# Hviezdy.net
KiCad netlist of a schematic drawn in EAGLE
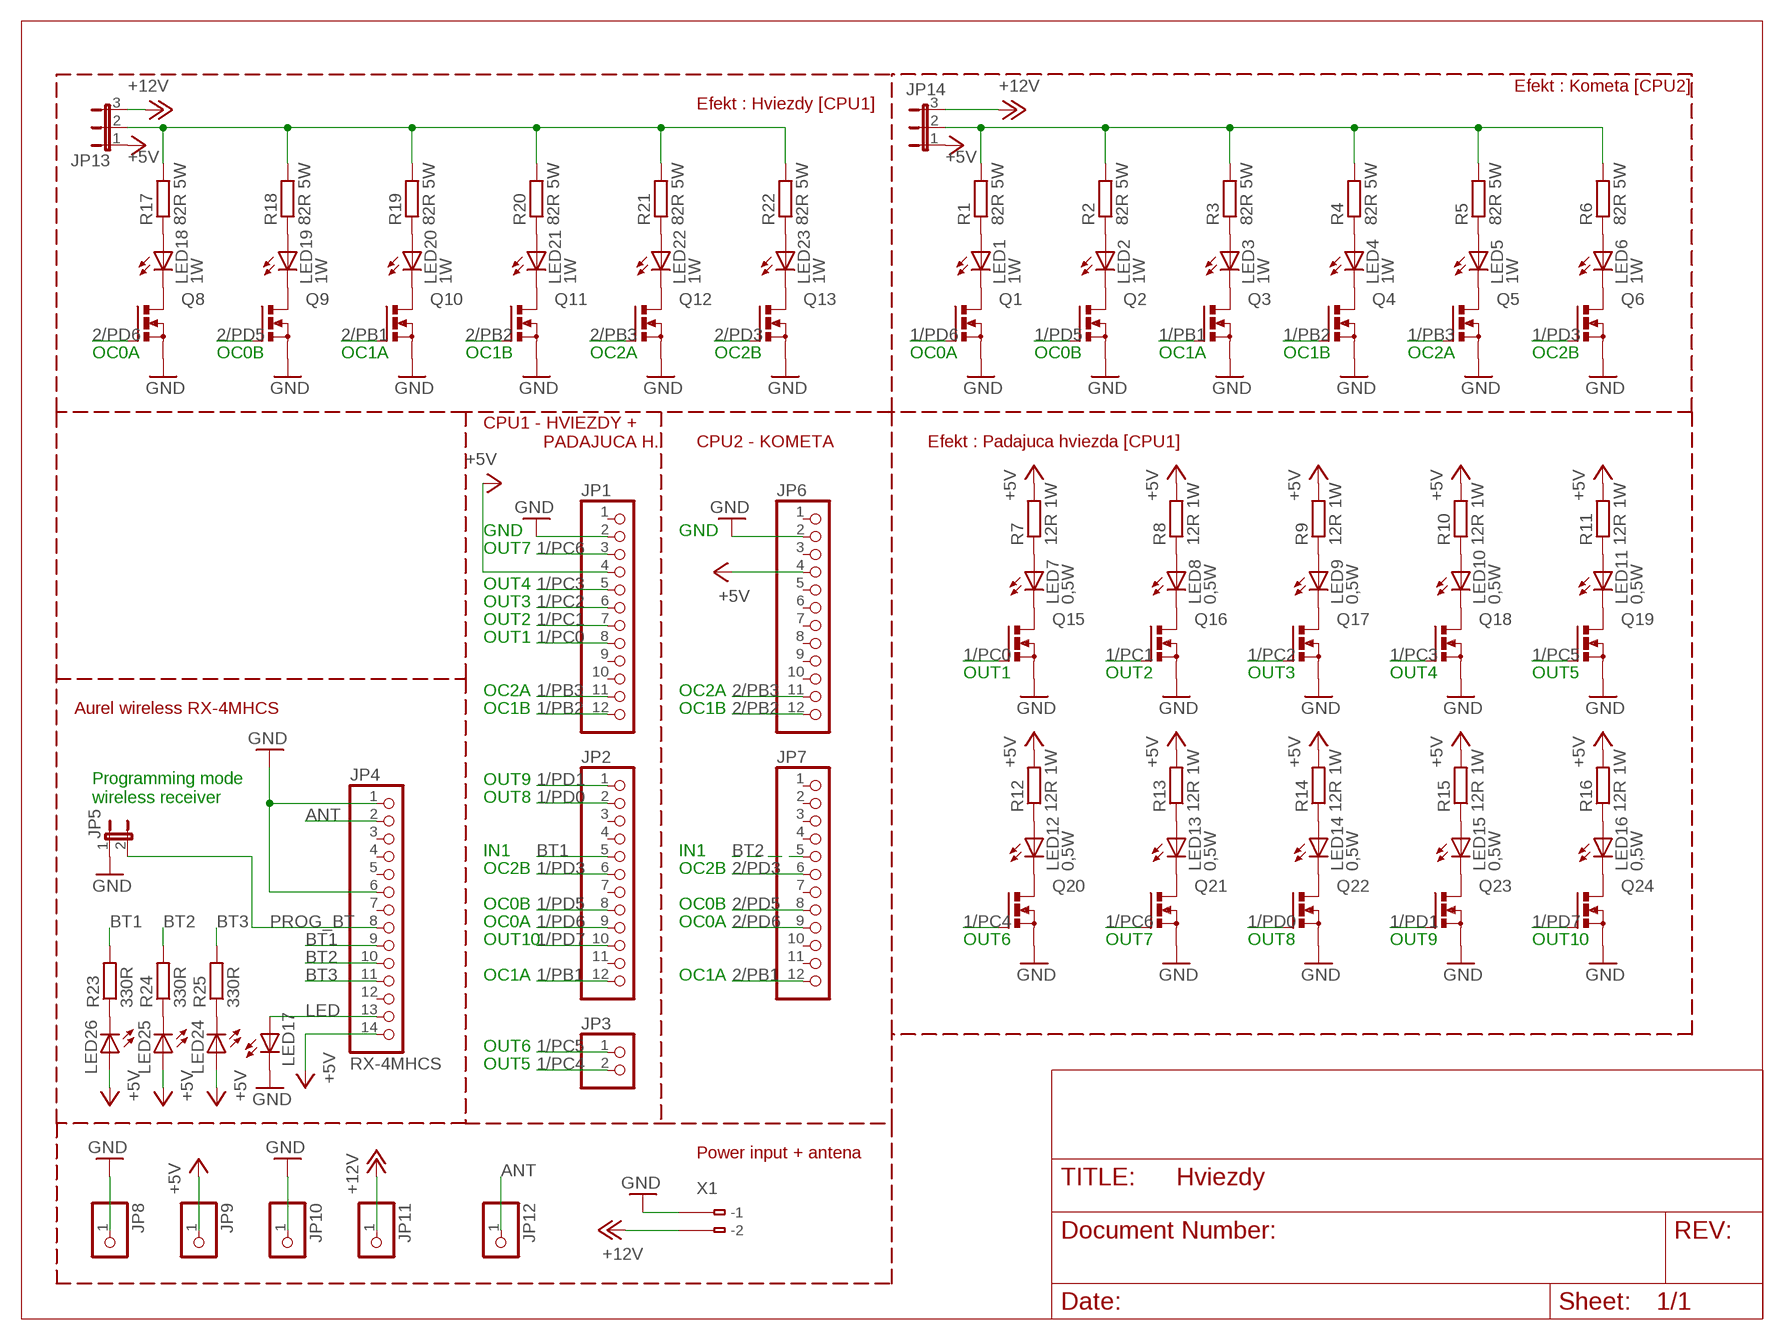
[diagram p0: schematic, sheet 1]

(export (version "E")
  (design (tool "Eeschema 10.0.6"))
  (components
    (comp (ref "JP1")
      (value "PINHD-1X12")
      (footprint "eagle-import:1X12")
      (libsource (lib "eagle-import") (part "PINHD-1X12"))
    )
    (comp (ref "JP2")
      (value "PINHD-1X12")
      (footprint "eagle-import:1X12")
      (libsource (lib "eagle-import") (part "PINHD-1X12"))
    )
    (comp (ref "JP3")
      (value "PINHD-1X2")
      (footprint "eagle-import:1X02")
      (libsource (lib "eagle-import") (part "PINHD-1X2"))
    )
    (comp (ref "JP4")
      (value "RX-4MHCS")
      (footprint "eagle-import:1X14")
      (libsource (lib "eagle-import") (part "PINHD-1X14"))
    )
    (comp (ref "JP5")
      (value "JP1E")
      (footprint "eagle-import:JP1")
      (libsource (lib "eagle-import") (part "JP1E"))
    )
    (comp (ref "JP6")
      (value "PINHD-1X12")
      (footprint "eagle-import:1X12")
      (libsource (lib "eagle-import") (part "PINHD-1X12"))
    )
    (comp (ref "JP7")
      (value "PINHD-1X12")
      (footprint "eagle-import:1X12")
      (libsource (lib "eagle-import") (part "PINHD-1X12"))
    )
    (comp (ref "JP8")
      (value "PINHD-1X1")
      (footprint "eagle-import:1X01")
      (libsource (lib "eagle-import") (part "PINHD-1X1"))
    )
    (comp (ref "JP9")
      (value "PINHD-1X1")
      (footprint "eagle-import:1X01")
      (libsource (lib "eagle-import") (part "PINHD-1X1"))
    )
    (comp (ref "JP10")
      (value "PINHD-1X1")
      (footprint "eagle-import:1X01")
      (libsource (lib "eagle-import") (part "PINHD-1X1"))
    )
    (comp (ref "JP11")
      (value "PINHD-1X1")
      (footprint "eagle-import:1X01")
      (libsource (lib "eagle-import") (part "PINHD-1X1"))
    )
    (comp (ref "JP12")
      (value "PINHD-1X1")
      (footprint "eagle-import:1X01")
      (libsource (lib "eagle-import") (part "PINHD-1X1"))
    )
    (comp (ref "JP13")
      (value "JP2E")
      (footprint "eagle-import:JP2")
      (libsource (lib "eagle-import") (part "JP2E"))
    )
    (comp (ref "JP14")
      (value "JP2E")
      (footprint "eagle-import:JP2")
      (libsource (lib "eagle-import") (part "JP2E"))
    )
    (comp (ref "LED1")
      (value "1W")
      (footprint "eagle-import:LED5MM")
      (libsource (lib "eagle-import") (part "LED5MM"))
    )
    (comp (ref "LED2")
      (value "1W")
      (footprint "eagle-import:LED5MM")
      (libsource (lib "eagle-import") (part "LED5MM"))
    )
    (comp (ref "LED3")
      (value "1W")
      (footprint "eagle-import:LED5MM")
      (libsource (lib "eagle-import") (part "LED5MM"))
    )
    (comp (ref "LED4")
      (value "1W")
      (footprint "eagle-import:LED5MM")
      (libsource (lib "eagle-import") (part "LED5MM"))
    )
    (comp (ref "LED5")
      (value "1W")
      (footprint "eagle-import:LED5MM")
      (libsource (lib "eagle-import") (part "LED5MM"))
    )
    (comp (ref "LED6")
      (value "1W")
      (footprint "eagle-import:LED5MM")
      (libsource (lib "eagle-import") (part "LED5MM"))
    )
    (comp (ref "LED7")
      (value "0,5W")
      (footprint "eagle-import:LED10MM")
      (libsource (lib "eagle-import") (part "LED10MM"))
    )
    (comp (ref "LED8")
      (value "0,5W")
      (footprint "eagle-import:LED10MM")
      (libsource (lib "eagle-import") (part "LED10MM"))
    )
    (comp (ref "LED9")
      (value "0,5W")
      (footprint "eagle-import:LED10MM")
      (libsource (lib "eagle-import") (part "LED10MM"))
    )
    (comp (ref "LED10")
      (value "0,5W")
      (footprint "eagle-import:LED10MM")
      (libsource (lib "eagle-import") (part "LED10MM"))
    )
    (comp (ref "LED11")
      (value "0,5W")
      (footprint "eagle-import:LED10MM")
      (libsource (lib "eagle-import") (part "LED10MM"))
    )
    (comp (ref "LED12")
      (value "0,5W")
      (footprint "eagle-import:LED10MM")
      (libsource (lib "eagle-import") (part "LED10MM"))
    )
    (comp (ref "LED13")
      (value "0,5W")
      (footprint "eagle-import:LED10MM")
      (libsource (lib "eagle-import") (part "LED10MM"))
    )
    (comp (ref "LED14")
      (value "0,5W")
      (footprint "eagle-import:LED10MM")
      (libsource (lib "eagle-import") (part "LED10MM"))
    )
    (comp (ref "LED15")
      (value "0,5W")
      (footprint "eagle-import:LED10MM")
      (libsource (lib "eagle-import") (part "LED10MM"))
    )
    (comp (ref "LED16")
      (value "0,5W")
      (footprint "eagle-import:LED10MM")
      (libsource (lib "eagle-import") (part "LED10MM"))
    )
    (comp (ref "LED17")
      (value "LED3MM")
      (footprint "eagle-import:LED3MM")
      (libsource (lib "eagle-import") (part "LED3MM"))
    )
    (comp (ref "LED18")
      (value "1W")
      (footprint "eagle-import:LED5MM")
      (libsource (lib "eagle-import") (part "LED5MM"))
    )
    (comp (ref "LED19")
      (value "1W")
      (footprint "eagle-import:LED5MM")
      (libsource (lib "eagle-import") (part "LED5MM"))
    )
    (comp (ref "LED20")
      (value "1W")
      (footprint "eagle-import:LED5MM")
      (libsource (lib "eagle-import") (part "LED5MM"))
    )
    (comp (ref "LED21")
      (value "1W")
      (footprint "eagle-import:LED5MM")
      (libsource (lib "eagle-import") (part "LED5MM"))
    )
    (comp (ref "LED22")
      (value "1W")
      (footprint "eagle-import:LED5MM")
      (libsource (lib "eagle-import") (part "LED5MM"))
    )
    (comp (ref "LED23")
      (value "1W")
      (footprint "eagle-import:LED5MM")
      (libsource (lib "eagle-import") (part "LED5MM"))
    )
    (comp (ref "LED24")
      (value "LED3MM")
      (footprint "eagle-import:LED3MM")
      (libsource (lib "eagle-import") (part "LED3MM"))
    )
    (comp (ref "LED25")
      (value "LED3MM")
      (footprint "eagle-import:LED3MM")
      (libsource (lib "eagle-import") (part "LED3MM"))
    )
    (comp (ref "LED26")
      (value "LED3MM")
      (footprint "eagle-import:LED3MM")
      (libsource (lib "eagle-import") (part "LED3MM"))
    )
    (comp (ref "Q1")
      (value "PMOSFET_NTO220BV")
      (footprint "eagle-import:TO220BV")
      (libsource (lib "eagle-import") (part "PMOSFET_NTO220BV"))
    )
    (comp (ref "Q2")
      (value "PMOSFET_NTO220BV")
      (footprint "eagle-import:TO220BV")
      (libsource (lib "eagle-import") (part "PMOSFET_NTO220BV"))
    )
    (comp (ref "Q3")
      (value "PMOSFET_NTO220BV")
      (footprint "eagle-import:TO220BV")
      (libsource (lib "eagle-import") (part "PMOSFET_NTO220BV"))
    )
    (comp (ref "Q4")
      (value "PMOSFET_NTO220BV")
      (footprint "eagle-import:TO220BV")
      (libsource (lib "eagle-import") (part "PMOSFET_NTO220BV"))
    )
    (comp (ref "Q5")
      (value "PMOSFET_NTO220BV")
      (footprint "eagle-import:TO220BV")
      (libsource (lib "eagle-import") (part "PMOSFET_NTO220BV"))
    )
    (comp (ref "Q6")
      (value "PMOSFET_NTO220BV")
      (footprint "eagle-import:TO220BV")
      (libsource (lib "eagle-import") (part "PMOSFET_NTO220BV"))
    )
    (comp (ref "Q8")
      (value "PMOSFET_NTO220BV")
      (footprint "eagle-import:TO220BV")
      (libsource (lib "eagle-import") (part "PMOSFET_NTO220BV"))
    )
    (comp (ref "Q9")
      (value "PMOSFET_NTO220BV")
      (footprint "eagle-import:TO220BV")
      (libsource (lib "eagle-import") (part "PMOSFET_NTO220BV"))
    )
    (comp (ref "Q10")
      (value "PMOSFET_NTO220BV")
      (footprint "eagle-import:TO220BV")
      (libsource (lib "eagle-import") (part "PMOSFET_NTO220BV"))
    )
    (comp (ref "Q11")
      (value "PMOSFET_NTO220BV")
      (footprint "eagle-import:TO220BV")
      (libsource (lib "eagle-import") (part "PMOSFET_NTO220BV"))
    )
    (comp (ref "Q12")
      (value "PMOSFET_NTO220BV")
      (footprint "eagle-import:TO220BV")
      (libsource (lib "eagle-import") (part "PMOSFET_NTO220BV"))
    )
    (comp (ref "Q13")
      (value "PMOSFET_NTO220BV")
      (footprint "eagle-import:TO220BV")
      (libsource (lib "eagle-import") (part "PMOSFET_NTO220BV"))
    )
    (comp (ref "Q15")
      (value "PMOSFET_NTO220BV")
      (footprint "eagle-import:TO220BV")
      (libsource (lib "eagle-import") (part "PMOSFET_NTO220BV"))
    )
    (comp (ref "Q16")
      (value "PMOSFET_NTO220BV")
      (footprint "eagle-import:TO220BV")
      (libsource (lib "eagle-import") (part "PMOSFET_NTO220BV"))
    )
    (comp (ref "Q17")
      (value "PMOSFET_NTO220BV")
      (footprint "eagle-import:TO220BV")
      (libsource (lib "eagle-import") (part "PMOSFET_NTO220BV"))
    )
    (comp (ref "Q18")
      (value "PMOSFET_NTO220BV")
      (footprint "eagle-import:TO220BV")
      (libsource (lib "eagle-import") (part "PMOSFET_NTO220BV"))
    )
    (comp (ref "Q19")
      (value "PMOSFET_NTO220BV")
      (footprint "eagle-import:TO220BV")
      (libsource (lib "eagle-import") (part "PMOSFET_NTO220BV"))
    )
    (comp (ref "Q20")
      (value "PMOSFET_NTO220BV")
      (footprint "eagle-import:TO220BV")
      (libsource (lib "eagle-import") (part "PMOSFET_NTO220BV"))
    )
    (comp (ref "Q21")
      (value "PMOSFET_NTO220BV")
      (footprint "eagle-import:TO220BV")
      (libsource (lib "eagle-import") (part "PMOSFET_NTO220BV"))
    )
    (comp (ref "Q22")
      (value "PMOSFET_NTO220BV")
      (footprint "eagle-import:TO220BV")
      (libsource (lib "eagle-import") (part "PMOSFET_NTO220BV"))
    )
    (comp (ref "Q23")
      (value "PMOSFET_NTO220BV")
      (footprint "eagle-import:TO220BV")
      (libsource (lib "eagle-import") (part "PMOSFET_NTO220BV"))
    )
    (comp (ref "Q24")
      (value "PMOSFET_NTO220BV")
      (footprint "eagle-import:TO220BV")
      (libsource (lib "eagle-import") (part "PMOSFET_NTO220BV"))
    )
    (comp (ref "R1")
      (value "82R 5W")
      (footprint "eagle-import:0922V")
      (libsource (lib "eagle-import") (part "R-EU_0922V"))
    )
    (comp (ref "R2")
      (value "82R 5W")
      (footprint "eagle-import:0922V")
      (libsource (lib "eagle-import") (part "R-EU_0922V"))
    )
    (comp (ref "R3")
      (value "82R 5W")
      (footprint "eagle-import:0922V")
      (libsource (lib "eagle-import") (part "R-EU_0922V"))
    )
    (comp (ref "R4")
      (value "82R 5W")
      (footprint "eagle-import:0922V")
      (libsource (lib "eagle-import") (part "R-EU_0922V"))
    )
    (comp (ref "R5")
      (value "82R 5W")
      (footprint "eagle-import:0922V")
      (libsource (lib "eagle-import") (part "R-EU_0922V"))
    )
    (comp (ref "R6")
      (value "82R 5W")
      (footprint "eagle-import:0922V")
      (libsource (lib "eagle-import") (part "R-EU_0922V"))
    )
    (comp (ref "R7")
      (value "12R 1W")
      (footprint "eagle-import:0309_12")
      (libsource (lib "eagle-import") (part "R-EU_0309/12"))
    )
    (comp (ref "R8")
      (value "12R 1W")
      (footprint "eagle-import:0309_12")
      (libsource (lib "eagle-import") (part "R-EU_0309/12"))
    )
    (comp (ref "R9")
      (value "12R 1W")
      (footprint "eagle-import:0309_12")
      (libsource (lib "eagle-import") (part "R-EU_0309/12"))
    )
    (comp (ref "R10")
      (value "12R 1W")
      (footprint "eagle-import:0309_12")
      (libsource (lib "eagle-import") (part "R-EU_0309/12"))
    )
    (comp (ref "R11")
      (value "12R 1W")
      (footprint "eagle-import:0309_12")
      (libsource (lib "eagle-import") (part "R-EU_0309/12"))
    )
    (comp (ref "R12")
      (value "12R 1W")
      (footprint "eagle-import:0309_12")
      (libsource (lib "eagle-import") (part "R-EU_0309/12"))
    )
    (comp (ref "R13")
      (value "12R 1W")
      (footprint "eagle-import:0309_12")
      (libsource (lib "eagle-import") (part "R-EU_0309/12"))
    )
    (comp (ref "R14")
      (value "12R 1W")
      (footprint "eagle-import:0309_12")
      (libsource (lib "eagle-import") (part "R-EU_0309/12"))
    )
    (comp (ref "R15")
      (value "12R 1W")
      (footprint "eagle-import:0309_12")
      (libsource (lib "eagle-import") (part "R-EU_0309/12"))
    )
    (comp (ref "R16")
      (value "12R 1W")
      (footprint "eagle-import:0309_12")
      (libsource (lib "eagle-import") (part "R-EU_0309/12"))
    )
    (comp (ref "R17")
      (value "82R 5W")
      (footprint "eagle-import:0922V")
      (libsource (lib "eagle-import") (part "R-EU_0922V"))
    )
    (comp (ref "R18")
      (value "82R 5W")
      (footprint "eagle-import:0922V")
      (libsource (lib "eagle-import") (part "R-EU_0922V"))
    )
    (comp (ref "R19")
      (value "82R 5W")
      (footprint "eagle-import:0922V")
      (libsource (lib "eagle-import") (part "R-EU_0922V"))
    )
    (comp (ref "R20")
      (value "82R 5W")
      (footprint "eagle-import:0922V")
      (libsource (lib "eagle-import") (part "R-EU_0922V"))
    )
    (comp (ref "R21")
      (value "82R 5W")
      (footprint "eagle-import:0922V")
      (libsource (lib "eagle-import") (part "R-EU_0922V"))
    )
    (comp (ref "R22")
      (value "82R 5W")
      (footprint "eagle-import:0922V")
      (libsource (lib "eagle-import") (part "R-EU_0922V"))
    )
    (comp (ref "R23")
      (value "330R")
      (footprint "eagle-import:0207_12")
      (libsource (lib "eagle-import") (part "resistor_R-EU_0207/12"))
    )
    (comp (ref "R24")
      (value "330R")
      (footprint "eagle-import:0207_12")
      (libsource (lib "eagle-import") (part "resistor_R-EU_0207/12"))
    )
    (comp (ref "R25")
      (value "330R")
      (footprint "eagle-import:0207_12")
      (libsource (lib "eagle-import") (part "resistor_R-EU_0207/12"))
    )
    (comp (ref "X1")
      (value "234-202")
      (footprint "eagle-import:234-202")
      (libsource (lib "eagle-import") (part "234-202"))
    )
  )
  (nets
    (net (code "1") (name "+5V") (class "Default")
      (node (ref "JP1") (pin "4") (pinfunction "4_4") (pintype "passive"))
      (node (ref "JP13") (pin "1") (pinfunction "1_1") (pintype "passive"))
      (node (ref "JP14") (pin "1") (pinfunction "1_1") (pintype "passive"))
      (node (ref "JP4") (pin "14") (pinfunction "14_14") (pintype "passive"))
      (node (ref "JP6") (pin "4") (pinfunction "4_4") (pintype "passive"))
      (node (ref "JP9") (pin "1") (pinfunction "1_1") (pintype "passive"))
      (node (ref "LED24") (pin "A") (pinfunction "A_A") (pintype "passive"))
      (node (ref "LED25") (pin "A") (pinfunction "A_A") (pintype "passive"))
      (node (ref "LED26") (pin "A") (pinfunction "A_A") (pintype "passive"))
      (node (ref "R10") (pin "2") (pinfunction "2_2") (pintype "passive"))
      (node (ref "R11") (pin "2") (pinfunction "2_2") (pintype "passive"))
      (node (ref "R12") (pin "2") (pinfunction "2_2") (pintype "passive"))
      (node (ref "R13") (pin "2") (pinfunction "2_2") (pintype "passive"))
      (node (ref "R14") (pin "2") (pinfunction "2_2") (pintype "passive"))
      (node (ref "R15") (pin "2") (pinfunction "2_2") (pintype "passive"))
      (node (ref "R16") (pin "2") (pinfunction "2_2") (pintype "passive"))
      (node (ref "R7") (pin "2") (pinfunction "2_2") (pintype "passive"))
      (node (ref "R8") (pin "2") (pinfunction "2_2") (pintype "passive"))
      (node (ref "R9") (pin "2") (pinfunction "2_2") (pintype "passive"))
    )
    (net (code "2") (name "+12V") (class "Default")
      (node (ref "JP11") (pin "1") (pinfunction "1_1") (pintype "passive"))
      (node (ref "JP13") (pin "3") (pinfunction "3_3") (pintype "passive"))
      (node (ref "JP14") (pin "3") (pinfunction "3_3") (pintype "passive"))
      (node (ref "X1") (pin "B2") (pinfunction "B-2_B2") (pintype "passive"))
    )
    (net (code "3") (name "/1{slash}PB1") (class "Default")
      (node (ref "JP2") (pin "12") (pinfunction "12_12") (pintype "passive"))
      (node (ref "Q3") (pin "G") (pinfunction "G_G") (pintype "passive"))
    )
    (net (code "4") (name "/1{slash}PB2") (class "Default")
      (node (ref "JP1") (pin "12") (pinfunction "12_12") (pintype "passive"))
      (node (ref "Q4") (pin "G") (pinfunction "G_G") (pintype "passive"))
    )
    (net (code "5") (name "/1{slash}PB3") (class "Default")
      (node (ref "JP1") (pin "11") (pinfunction "11_11") (pintype "passive"))
      (node (ref "Q5") (pin "G") (pinfunction "G_G") (pintype "passive"))
    )
    (net (code "6") (name "/1{slash}PC0") (class "Default")
      (node (ref "JP1") (pin "8") (pinfunction "8_8") (pintype "passive"))
      (node (ref "Q15") (pin "G") (pinfunction "G_G") (pintype "passive"))
    )
    (net (code "7") (name "/1{slash}PC1") (class "Default")
      (node (ref "JP1") (pin "7") (pinfunction "7_7") (pintype "passive"))
      (node (ref "Q16") (pin "G") (pinfunction "G_G") (pintype "passive"))
    )
    (net (code "8") (name "/1{slash}PC2") (class "Default")
      (node (ref "JP1") (pin "6") (pinfunction "6_6") (pintype "passive"))
      (node (ref "Q17") (pin "G") (pinfunction "G_G") (pintype "passive"))
    )
    (net (code "9") (name "/1{slash}PC3") (class "Default")
      (node (ref "JP1") (pin "5") (pinfunction "5_5") (pintype "passive"))
      (node (ref "Q18") (pin "G") (pinfunction "G_G") (pintype "passive"))
    )
    (net (code "10") (name "/1{slash}PC4") (class "Default")
      (node (ref "JP3") (pin "2") (pinfunction "2_2") (pintype "passive"))
      (node (ref "Q20") (pin "G") (pinfunction "G_G") (pintype "passive"))
    )
    (net (code "11") (name "/1{slash}PC5") (class "Default")
      (node (ref "JP3") (pin "1") (pinfunction "1_1") (pintype "passive"))
      (node (ref "Q19") (pin "G") (pinfunction "G_G") (pintype "passive"))
    )
    (net (code "12") (name "/1{slash}PC6") (class "Default")
      (node (ref "JP1") (pin "3") (pinfunction "3_3") (pintype "passive"))
      (node (ref "Q21") (pin "G") (pinfunction "G_G") (pintype "passive"))
    )
    (net (code "13") (name "/1{slash}PD0") (class "Default")
      (node (ref "JP2") (pin "2") (pinfunction "2_2") (pintype "passive"))
      (node (ref "Q22") (pin "G") (pinfunction "G_G") (pintype "passive"))
    )
    (net (code "14") (name "/1{slash}PD1") (class "Default")
      (node (ref "JP2") (pin "1") (pinfunction "1_1") (pintype "passive"))
      (node (ref "Q23") (pin "G") (pinfunction "G_G") (pintype "passive"))
    )
    (net (code "15") (name "/1{slash}PD3") (class "Default")
      (node (ref "JP2") (pin "6") (pinfunction "6_6") (pintype "passive"))
      (node (ref "Q6") (pin "G") (pinfunction "G_G") (pintype "passive"))
    )
    (net (code "16") (name "/1{slash}PD5") (class "Default")
      (node (ref "JP2") (pin "8") (pinfunction "8_8") (pintype "passive"))
      (node (ref "Q2") (pin "G") (pinfunction "G_G") (pintype "passive"))
    )
    (net (code "17") (name "/1{slash}PD6") (class "Default")
      (node (ref "JP2") (pin "9") (pinfunction "9_9") (pintype "passive"))
      (node (ref "Q1") (pin "G") (pinfunction "G_G") (pintype "passive"))
    )
    (net (code "18") (name "/1{slash}PD7") (class "Default")
      (node (ref "JP2") (pin "10") (pinfunction "10_10") (pintype "passive"))
      (node (ref "Q24") (pin "G") (pinfunction "G_G") (pintype "passive"))
    )
    (net (code "19") (name "/2{slash}PB1") (class "Default")
      (node (ref "JP7") (pin "12") (pinfunction "12_12") (pintype "passive"))
      (node (ref "Q10") (pin "G") (pinfunction "G_G") (pintype "passive"))
    )
    (net (code "20") (name "/2{slash}PB2") (class "Default")
      (node (ref "JP6") (pin "12") (pinfunction "12_12") (pintype "passive"))
      (node (ref "Q11") (pin "G") (pinfunction "G_G") (pintype "passive"))
    )
    (net (code "21") (name "/2{slash}PB3") (class "Default")
      (node (ref "JP6") (pin "11") (pinfunction "11_11") (pintype "passive"))
      (node (ref "Q12") (pin "G") (pinfunction "G_G") (pintype "passive"))
    )
    (net (code "22") (name "/2{slash}PD3") (class "Default")
      (node (ref "JP7") (pin "6") (pinfunction "6_6") (pintype "passive"))
      (node (ref "Q13") (pin "G") (pinfunction "G_G") (pintype "passive"))
    )
    (net (code "23") (name "/2{slash}PD5") (class "Default")
      (node (ref "JP7") (pin "8") (pinfunction "8_8") (pintype "passive"))
      (node (ref "Q9") (pin "G") (pinfunction "G_G") (pintype "passive"))
    )
    (net (code "24") (name "/2{slash}PD6") (class "Default")
      (node (ref "JP7") (pin "9") (pinfunction "9_9") (pintype "passive"))
      (node (ref "Q8") (pin "G") (pinfunction "G_G") (pintype "passive"))
    )
    (net (code "25") (name "/ANT") (class "Default")
      (node (ref "JP12") (pin "1") (pinfunction "1_1") (pintype "passive"))
      (node (ref "JP4") (pin "2") (pinfunction "2_2") (pintype "passive"))
    )
    (net (code "26") (name "/BT1") (class "Default")
      (node (ref "JP2") (pin "5") (pinfunction "5_5") (pintype "passive"))
      (node (ref "JP4") (pin "9") (pinfunction "9_9") (pintype "passive"))
      (node (ref "R23") (pin "2") (pinfunction "2_2") (pintype "passive"))
    )
    (net (code "27") (name "/BT2") (class "Default")
      (node (ref "JP4") (pin "10") (pinfunction "10_10") (pintype "passive"))
      (node (ref "JP7") (pin "5") (pinfunction "5_5") (pintype "passive"))
      (node (ref "R24") (pin "2") (pinfunction "2_2") (pintype "passive"))
    )
    (net (code "28") (name "/BT3") (class "Default")
      (node (ref "JP4") (pin "11") (pinfunction "11_11") (pintype "passive"))
      (node (ref "R25") (pin "2") (pinfunction "2_2") (pintype "passive"))
    )
    (net (code "29") (name "/LED") (class "Default")
      (node (ref "JP4") (pin "13") (pinfunction "13_13") (pintype "passive"))
      (node (ref "LED17") (pin "A") (pinfunction "A_A") (pintype "passive"))
    )
    (net (code "30") (name "/PROG_BT") (class "Default")
      (node (ref "JP4") (pin "8") (pinfunction "8_8") (pintype "passive"))
      (node (ref "JP5") (pin "2") (pinfunction "2_2") (pintype "passive"))
    )
    (net (code "31") (name "GND") (class "Default")
      (node (ref "JP1") (pin "2") (pinfunction "2_2") (pintype "passive"))
      (node (ref "JP10") (pin "1") (pinfunction "1_1") (pintype "passive"))
      (node (ref "JP4") (pin "1") (pinfunction "1_1") (pintype "passive"))
      (node (ref "JP4") (pin "6") (pinfunction "6_6") (pintype "passive"))
      (node (ref "JP5") (pin "1") (pinfunction "1_1") (pintype "passive"))
      (node (ref "JP6") (pin "2") (pinfunction "2_2") (pintype "passive"))
      (node (ref "JP8") (pin "1") (pinfunction "1_1") (pintype "passive"))
      (node (ref "LED17") (pin "K") (pinfunction "C_K") (pintype "passive"))
      (node (ref "Q1") (pin "S") (pinfunction "S_S") (pintype "passive"))
      (node (ref "Q10") (pin "S") (pinfunction "S_S") (pintype "passive"))
      (node (ref "Q11") (pin "S") (pinfunction "S_S") (pintype "passive"))
      (node (ref "Q12") (pin "S") (pinfunction "S_S") (pintype "passive"))
      (node (ref "Q13") (pin "S") (pinfunction "S_S") (pintype "passive"))
      (node (ref "Q15") (pin "S") (pinfunction "S_S") (pintype "passive"))
      (node (ref "Q16") (pin "S") (pinfunction "S_S") (pintype "passive"))
      (node (ref "Q17") (pin "S") (pinfunction "S_S") (pintype "passive"))
      (node (ref "Q18") (pin "S") (pinfunction "S_S") (pintype "passive"))
      (node (ref "Q19") (pin "S") (pinfunction "S_S") (pintype "passive"))
      (node (ref "Q2") (pin "S") (pinfunction "S_S") (pintype "passive"))
      (node (ref "Q20") (pin "S") (pinfunction "S_S") (pintype "passive"))
      (node (ref "Q21") (pin "S") (pinfunction "S_S") (pintype "passive"))
      (node (ref "Q22") (pin "S") (pinfunction "S_S") (pintype "passive"))
      (node (ref "Q23") (pin "S") (pinfunction "S_S") (pintype "passive"))
      (node (ref "Q24") (pin "S") (pinfunction "S_S") (pintype "passive"))
      (node (ref "Q3") (pin "S") (pinfunction "S_S") (pintype "passive"))
      (node (ref "Q4") (pin "S") (pinfunction "S_S") (pintype "passive"))
      (node (ref "Q5") (pin "S") (pinfunction "S_S") (pintype "passive"))
      (node (ref "Q6") (pin "S") (pinfunction "S_S") (pintype "passive"))
      (node (ref "Q8") (pin "S") (pinfunction "S_S") (pintype "passive"))
      (node (ref "Q9") (pin "S") (pinfunction "S_S") (pintype "passive"))
      (node (ref "X1") (pin "B1") (pinfunction "B-1_B1") (pintype "passive"))
    )
    (net (code "32") (name "Net-(JP13-Pad2)") (class "Default")
      (node (ref "JP13") (pin "2") (pinfunction "2_2") (pintype "passive"))
      (node (ref "R17") (pin "2") (pinfunction "2_2") (pintype "passive"))
      (node (ref "R18") (pin "2") (pinfunction "2_2") (pintype "passive"))
      (node (ref "R19") (pin "2") (pinfunction "2_2") (pintype "passive"))
      (node (ref "R20") (pin "2") (pinfunction "2_2") (pintype "passive"))
      (node (ref "R21") (pin "2") (pinfunction "2_2") (pintype "passive"))
      (node (ref "R22") (pin "2") (pinfunction "2_2") (pintype "passive"))
    )
    (net (code "33") (name "Net-(JP14-Pad2)") (class "Default")
      (node (ref "JP14") (pin "2") (pinfunction "2_2") (pintype "passive"))
      (node (ref "R1") (pin "2") (pinfunction "2_2") (pintype "passive"))
      (node (ref "R2") (pin "2") (pinfunction "2_2") (pintype "passive"))
      (node (ref "R3") (pin "2") (pinfunction "2_2") (pintype "passive"))
      (node (ref "R4") (pin "2") (pinfunction "2_2") (pintype "passive"))
      (node (ref "R5") (pin "2") (pinfunction "2_2") (pintype "passive"))
      (node (ref "R6") (pin "2") (pinfunction "2_2") (pintype "passive"))
    )
    (net (code "34") (name "Net-(LED1-C)") (class "Default")
      (node (ref "LED1") (pin "K") (pinfunction "C_K") (pintype "passive"))
      (node (ref "Q1") (pin "D") (pinfunction "D_D") (pintype "passive"))
    )
    (net (code "35") (name "Net-(LED1-PadA)") (class "Default")
      (node (ref "LED1") (pin "A") (pinfunction "A_A") (pintype "passive"))
      (node (ref "R1") (pin "1") (pinfunction "1_1") (pintype "passive"))
    )
    (net (code "36") (name "Net-(LED2-C)") (class "Default")
      (node (ref "LED2") (pin "K") (pinfunction "C_K") (pintype "passive"))
      (node (ref "Q2") (pin "D") (pinfunction "D_D") (pintype "passive"))
    )
    (net (code "37") (name "Net-(LED2-PadA)") (class "Default")
      (node (ref "LED2") (pin "A") (pinfunction "A_A") (pintype "passive"))
      (node (ref "R2") (pin "1") (pinfunction "1_1") (pintype "passive"))
    )
    (net (code "38") (name "Net-(LED3-C)") (class "Default")
      (node (ref "LED3") (pin "K") (pinfunction "C_K") (pintype "passive"))
      (node (ref "Q3") (pin "D") (pinfunction "D_D") (pintype "passive"))
    )
    (net (code "39") (name "Net-(LED3-PadA)") (class "Default")
      (node (ref "LED3") (pin "A") (pinfunction "A_A") (pintype "passive"))
      (node (ref "R3") (pin "1") (pinfunction "1_1") (pintype "passive"))
    )
    (net (code "40") (name "Net-(LED4-C)") (class "Default")
      (node (ref "LED4") (pin "K") (pinfunction "C_K") (pintype "passive"))
      (node (ref "Q4") (pin "D") (pinfunction "D_D") (pintype "passive"))
    )
    (net (code "41") (name "Net-(LED4-PadA)") (class "Default")
      (node (ref "LED4") (pin "A") (pinfunction "A_A") (pintype "passive"))
      (node (ref "R4") (pin "1") (pinfunction "1_1") (pintype "passive"))
    )
    (net (code "42") (name "Net-(LED5-C)") (class "Default")
      (node (ref "LED5") (pin "K") (pinfunction "C_K") (pintype "passive"))
      (node (ref "Q5") (pin "D") (pinfunction "D_D") (pintype "passive"))
    )
    (net (code "43") (name "Net-(LED5-PadA)") (class "Default")
      (node (ref "LED5") (pin "A") (pinfunction "A_A") (pintype "passive"))
      (node (ref "R5") (pin "1") (pinfunction "1_1") (pintype "passive"))
    )
    (net (code "44") (name "Net-(LED6-C)") (class "Default")
      (node (ref "LED6") (pin "K") (pinfunction "C_K") (pintype "passive"))
      (node (ref "Q6") (pin "D") (pinfunction "D_D") (pintype "passive"))
    )
    (net (code "45") (name "Net-(LED6-PadA)") (class "Default")
      (node (ref "LED6") (pin "A") (pinfunction "A_A") (pintype "passive"))
      (node (ref "R6") (pin "1") (pinfunction "1_1") (pintype "passive"))
    )
    (net (code "46") (name "Net-(LED7-C)") (class "Default")
      (node (ref "LED7") (pin "K") (pinfunction "C_K") (pintype "passive"))
      (node (ref "Q15") (pin "D") (pinfunction "D_D") (pintype "passive"))
    )
    (net (code "47") (name "Net-(LED7-PadA)") (class "Default")
      (node (ref "LED7") (pin "A") (pinfunction "A_A") (pintype "passive"))
      (node (ref "R7") (pin "1") (pinfunction "1_1") (pintype "passive"))
    )
    (net (code "48") (name "Net-(LED8-C)") (class "Default")
      (node (ref "LED8") (pin "K") (pinfunction "C_K") (pintype "passive"))
      (node (ref "Q16") (pin "D") (pinfunction "D_D") (pintype "passive"))
    )
    (net (code "49") (name "Net-(LED8-PadA)") (class "Default")
      (node (ref "LED8") (pin "A") (pinfunction "A_A") (pintype "passive"))
      (node (ref "R8") (pin "1") (pinfunction "1_1") (pintype "passive"))
    )
    (net (code "50") (name "Net-(LED9-C)") (class "Default")
      (node (ref "LED9") (pin "K") (pinfunction "C_K") (pintype "passive"))
      (node (ref "Q17") (pin "D") (pinfunction "D_D") (pintype "passive"))
    )
    (net (code "51") (name "Net-(LED9-PadA)") (class "Default")
      (node (ref "LED9") (pin "A") (pinfunction "A_A") (pintype "passive"))
      (node (ref "R9") (pin "1") (pinfunction "1_1") (pintype "passive"))
    )
    (net (code "52") (name "Net-(LED10-C)") (class "Default")
      (node (ref "LED10") (pin "K") (pinfunction "C_K") (pintype "passive"))
      (node (ref "Q18") (pin "D") (pinfunction "D_D") (pintype "passive"))
    )
    (net (code "53") (name "Net-(LED10-PadA)") (class "Default")
      (node (ref "LED10") (pin "A") (pinfunction "A_A") (pintype "passive"))
      (node (ref "R10") (pin "1") (pinfunction "1_1") (pintype "passive"))
    )
    (net (code "54") (name "Net-(LED11-C)") (class "Default")
      (node (ref "LED11") (pin "K") (pinfunction "C_K") (pintype "passive"))
      (node (ref "Q19") (pin "D") (pinfunction "D_D") (pintype "passive"))
    )
    (net (code "55") (name "Net-(LED11-PadA)") (class "Default")
      (node (ref "LED11") (pin "A") (pinfunction "A_A") (pintype "passive"))
      (node (ref "R11") (pin "1") (pinfunction "1_1") (pintype "passive"))
    )
    (net (code "56") (name "Net-(LED12-C)") (class "Default")
      (node (ref "LED12") (pin "K") (pinfunction "C_K") (pintype "passive"))
      (node (ref "Q20") (pin "D") (pinfunction "D_D") (pintype "passive"))
    )
    (net (code "57") (name "Net-(LED12-PadA)") (class "Default")
      (node (ref "LED12") (pin "A") (pinfunction "A_A") (pintype "passive"))
      (node (ref "R12") (pin "1") (pinfunction "1_1") (pintype "passive"))
    )
    (net (code "58") (name "Net-(LED13-C)") (class "Default")
      (node (ref "LED13") (pin "K") (pinfunction "C_K") (pintype "passive"))
      (node (ref "Q21") (pin "D") (pinfunction "D_D") (pintype "passive"))
    )
    (net (code "59") (name "Net-(LED13-PadA)") (class "Default")
      (node (ref "LED13") (pin "A") (pinfunction "A_A") (pintype "passive"))
      (node (ref "R13") (pin "1") (pinfunction "1_1") (pintype "passive"))
    )
    (net (code "60") (name "Net-(LED14-C)") (class "Default")
      (node (ref "LED14") (pin "K") (pinfunction "C_K") (pintype "passive"))
      (node (ref "Q22") (pin "D") (pinfunction "D_D") (pintype "passive"))
    )
    (net (code "61") (name "Net-(LED14-PadA)") (class "Default")
      (node (ref "LED14") (pin "A") (pinfunction "A_A") (pintype "passive"))
      (node (ref "R14") (pin "1") (pinfunction "1_1") (pintype "passive"))
    )
    (net (code "62") (name "Net-(LED15-C)") (class "Default")
      (node (ref "LED15") (pin "K") (pinfunction "C_K") (pintype "passive"))
      (node (ref "Q23") (pin "D") (pinfunction "D_D") (pintype "passive"))
    )
    (net (code "63") (name "Net-(LED15-PadA)") (class "Default")
      (node (ref "LED15") (pin "A") (pinfunction "A_A") (pintype "passive"))
      (node (ref "R15") (pin "1") (pinfunction "1_1") (pintype "passive"))
    )
    (net (code "64") (name "Net-(LED16-C)") (class "Default")
      (node (ref "LED16") (pin "K") (pinfunction "C_K") (pintype "passive"))
      (node (ref "Q24") (pin "D") (pinfunction "D_D") (pintype "passive"))
    )
    (net (code "65") (name "Net-(LED16-PadA)") (class "Default")
      (node (ref "LED16") (pin "A") (pinfunction "A_A") (pintype "passive"))
      (node (ref "R16") (pin "1") (pinfunction "1_1") (pintype "passive"))
    )
    (net (code "66") (name "Net-(LED18-C)") (class "Default")
      (node (ref "LED18") (pin "K") (pinfunction "C_K") (pintype "passive"))
      (node (ref "Q8") (pin "D") (pinfunction "D_D") (pintype "passive"))
    )
    (net (code "67") (name "Net-(LED18-PadA)") (class "Default")
      (node (ref "LED18") (pin "A") (pinfunction "A_A") (pintype "passive"))
      (node (ref "R17") (pin "1") (pinfunction "1_1") (pintype "passive"))
    )
    (net (code "68") (name "Net-(LED19-C)") (class "Default")
      (node (ref "LED19") (pin "K") (pinfunction "C_K") (pintype "passive"))
      (node (ref "Q9") (pin "D") (pinfunction "D_D") (pintype "passive"))
    )
    (net (code "69") (name "Net-(LED19-PadA)") (class "Default")
      (node (ref "LED19") (pin "A") (pinfunction "A_A") (pintype "passive"))
      (node (ref "R18") (pin "1") (pinfunction "1_1") (pintype "passive"))
    )
    (net (code "70") (name "Net-(LED20-C)") (class "Default")
      (node (ref "LED20") (pin "K") (pinfunction "C_K") (pintype "passive"))
      (node (ref "Q10") (pin "D") (pinfunction "D_D") (pintype "passive"))
    )
    (net (code "71") (name "Net-(LED20-PadA)") (class "Default")
      (node (ref "LED20") (pin "A") (pinfunction "A_A") (pintype "passive"))
      (node (ref "R19") (pin "1") (pinfunction "1_1") (pintype "passive"))
    )
    (net (code "72") (name "Net-(LED21-C)") (class "Default")
      (node (ref "LED21") (pin "K") (pinfunction "C_K") (pintype "passive"))
      (node (ref "Q11") (pin "D") (pinfunction "D_D") (pintype "passive"))
    )
    (net (code "73") (name "Net-(LED21-PadA)") (class "Default")
      (node (ref "LED21") (pin "A") (pinfunction "A_A") (pintype "passive"))
      (node (ref "R20") (pin "1") (pinfunction "1_1") (pintype "passive"))
    )
    (net (code "74") (name "Net-(LED22-C)") (class "Default")
      (node (ref "LED22") (pin "K") (pinfunction "C_K") (pintype "passive"))
      (node (ref "Q12") (pin "D") (pinfunction "D_D") (pintype "passive"))
    )
    (net (code "75") (name "Net-(LED22-PadA)") (class "Default")
      (node (ref "LED22") (pin "A") (pinfunction "A_A") (pintype "passive"))
      (node (ref "R21") (pin "1") (pinfunction "1_1") (pintype "passive"))
    )
    (net (code "76") (name "Net-(LED23-C)") (class "Default")
      (node (ref "LED23") (pin "K") (pinfunction "C_K") (pintype "passive"))
      (node (ref "Q13") (pin "D") (pinfunction "D_D") (pintype "passive"))
    )
    (net (code "77") (name "Net-(LED23-PadA)") (class "Default")
      (node (ref "LED23") (pin "A") (pinfunction "A_A") (pintype "passive"))
      (node (ref "R22") (pin "1") (pinfunction "1_1") (pintype "passive"))
    )
    (net (code "78") (name "Net-(LED24-C)") (class "Default")
      (node (ref "LED24") (pin "K") (pinfunction "C_K") (pintype "passive"))
      (node (ref "R25") (pin "1") (pinfunction "1_1") (pintype "passive"))
    )
    (net (code "79") (name "Net-(LED25-C)") (class "Default")
      (node (ref "LED25") (pin "K") (pinfunction "C_K") (pintype "passive"))
      (node (ref "R24") (pin "1") (pinfunction "1_1") (pintype "passive"))
    )
    (net (code "80") (name "Net-(LED26-C)") (class "Default")
      (node (ref "LED26") (pin "K") (pinfunction "C_K") (pintype "passive"))
      (node (ref "R23") (pin "1") (pinfunction "1_1") (pintype "passive"))
    )
    (net (code "81") (name "unconnected-(JP1-Pad1)") (class "Default")
      (node (ref "JP1") (pin "1") (pinfunction "1_1") (pintype "passive"))
    )
    (net (code "82") (name "unconnected-(JP1-Pad9)") (class "Default")
      (node (ref "JP1") (pin "9") (pinfunction "9_9") (pintype "passive"))
    )
    (net (code "83") (name "unconnected-(JP1-Pad10)") (class "Default")
      (node (ref "JP1") (pin "10") (pinfunction "10_10") (pintype "passive"))
    )
    (net (code "84") (name "unconnected-(JP2-Pad3)") (class "Default")
      (node (ref "JP2") (pin "3") (pinfunction "3_3") (pintype "passive"))
    )
    (net (code "85") (name "unconnected-(JP2-Pad4)") (class "Default")
      (node (ref "JP2") (pin "4") (pinfunction "4_4") (pintype "passive"))
    )
    (net (code "86") (name "unconnected-(JP2-Pad7)") (class "Default")
      (node (ref "JP2") (pin "7") (pinfunction "7_7") (pintype "passive"))
    )
    (net (code "87") (name "unconnected-(JP2-Pad11)") (class "Default")
      (node (ref "JP2") (pin "11") (pinfunction "11_11") (pintype "passive"))
    )
    (net (code "88") (name "unconnected-(JP4-Pad3)") (class "Default")
      (node (ref "JP4") (pin "3") (pinfunction "3_3") (pintype "passive"))
    )
    (net (code "89") (name "unconnected-(JP4-Pad4)") (class "Default")
      (node (ref "JP4") (pin "4") (pinfunction "4_4") (pintype "passive"))
    )
    (net (code "90") (name "unconnected-(JP4-Pad5)") (class "Default")
      (node (ref "JP4") (pin "5") (pinfunction "5_5") (pintype "passive"))
    )
    (net (code "91") (name "unconnected-(JP4-Pad7)") (class "Default")
      (node (ref "JP4") (pin "7") (pinfunction "7_7") (pintype "passive"))
    )
    (net (code "92") (name "unconnected-(JP4-Pad12)") (class "Default")
      (node (ref "JP4") (pin "12") (pinfunction "12_12") (pintype "passive"))
    )
    (net (code "93") (name "unconnected-(JP6-Pad1)") (class "Default")
      (node (ref "JP6") (pin "1") (pinfunction "1_1") (pintype "passive"))
    )
    (net (code "94") (name "unconnected-(JP6-Pad3)") (class "Default")
      (node (ref "JP6") (pin "3") (pinfunction "3_3") (pintype "passive"))
    )
    (net (code "95") (name "unconnected-(JP6-Pad5)") (class "Default")
      (node (ref "JP6") (pin "5") (pinfunction "5_5") (pintype "passive"))
    )
    (net (code "96") (name "unconnected-(JP6-Pad6)") (class "Default")
      (node (ref "JP6") (pin "6") (pinfunction "6_6") (pintype "passive"))
    )
    (net (code "97") (name "unconnected-(JP6-Pad7)") (class "Default")
      (node (ref "JP6") (pin "7") (pinfunction "7_7") (pintype "passive"))
    )
    (net (code "98") (name "unconnected-(JP6-Pad8)") (class "Default")
      (node (ref "JP6") (pin "8") (pinfunction "8_8") (pintype "passive"))
    )
    (net (code "99") (name "unconnected-(JP6-Pad9)") (class "Default")
      (node (ref "JP6") (pin "9") (pinfunction "9_9") (pintype "passive"))
    )
    (net (code "100") (name "unconnected-(JP6-Pad10)") (class "Default")
      (node (ref "JP6") (pin "10") (pinfunction "10_10") (pintype "passive"))
    )
    (net (code "101") (name "unconnected-(JP7-Pad1)") (class "Default")
      (node (ref "JP7") (pin "1") (pinfunction "1_1") (pintype "passive"))
    )
    (net (code "102") (name "unconnected-(JP7-Pad2)") (class "Default")
      (node (ref "JP7") (pin "2") (pinfunction "2_2") (pintype "passive"))
    )
    (net (code "103") (name "unconnected-(JP7-Pad3)") (class "Default")
      (node (ref "JP7") (pin "3") (pinfunction "3_3") (pintype "passive"))
    )
    (net (code "104") (name "unconnected-(JP7-Pad4)") (class "Default")
      (node (ref "JP7") (pin "4") (pinfunction "4_4") (pintype "passive"))
    )
    (net (code "105") (name "unconnected-(JP7-Pad7)") (class "Default")
      (node (ref "JP7") (pin "7") (pinfunction "7_7") (pintype "passive"))
    )
    (net (code "106") (name "unconnected-(JP7-Pad10)") (class "Default")
      (node (ref "JP7") (pin "10") (pinfunction "10_10") (pintype "passive"))
    )
    (net (code "107") (name "unconnected-(JP7-Pad11)") (class "Default")
      (node (ref "JP7") (pin "11") (pinfunction "11_11") (pintype "passive"))
    )
    (net (code "108") (name "unconnected-(X1--1-PadA1)") (class "Default")
      (node (ref "X1") (pin "A1") (pinfunction "-1_A1") (pintype "passive"))
    )
    (net (code "109") (name "unconnected-(X1--2-PadA2)") (class "Default")
      (node (ref "X1") (pin "A2") (pinfunction "-2_A2") (pintype "passive"))
    )
  )
)
